# GNSS_OCXO.net
KiCad netlist of a schematic drawn in Altium Designer
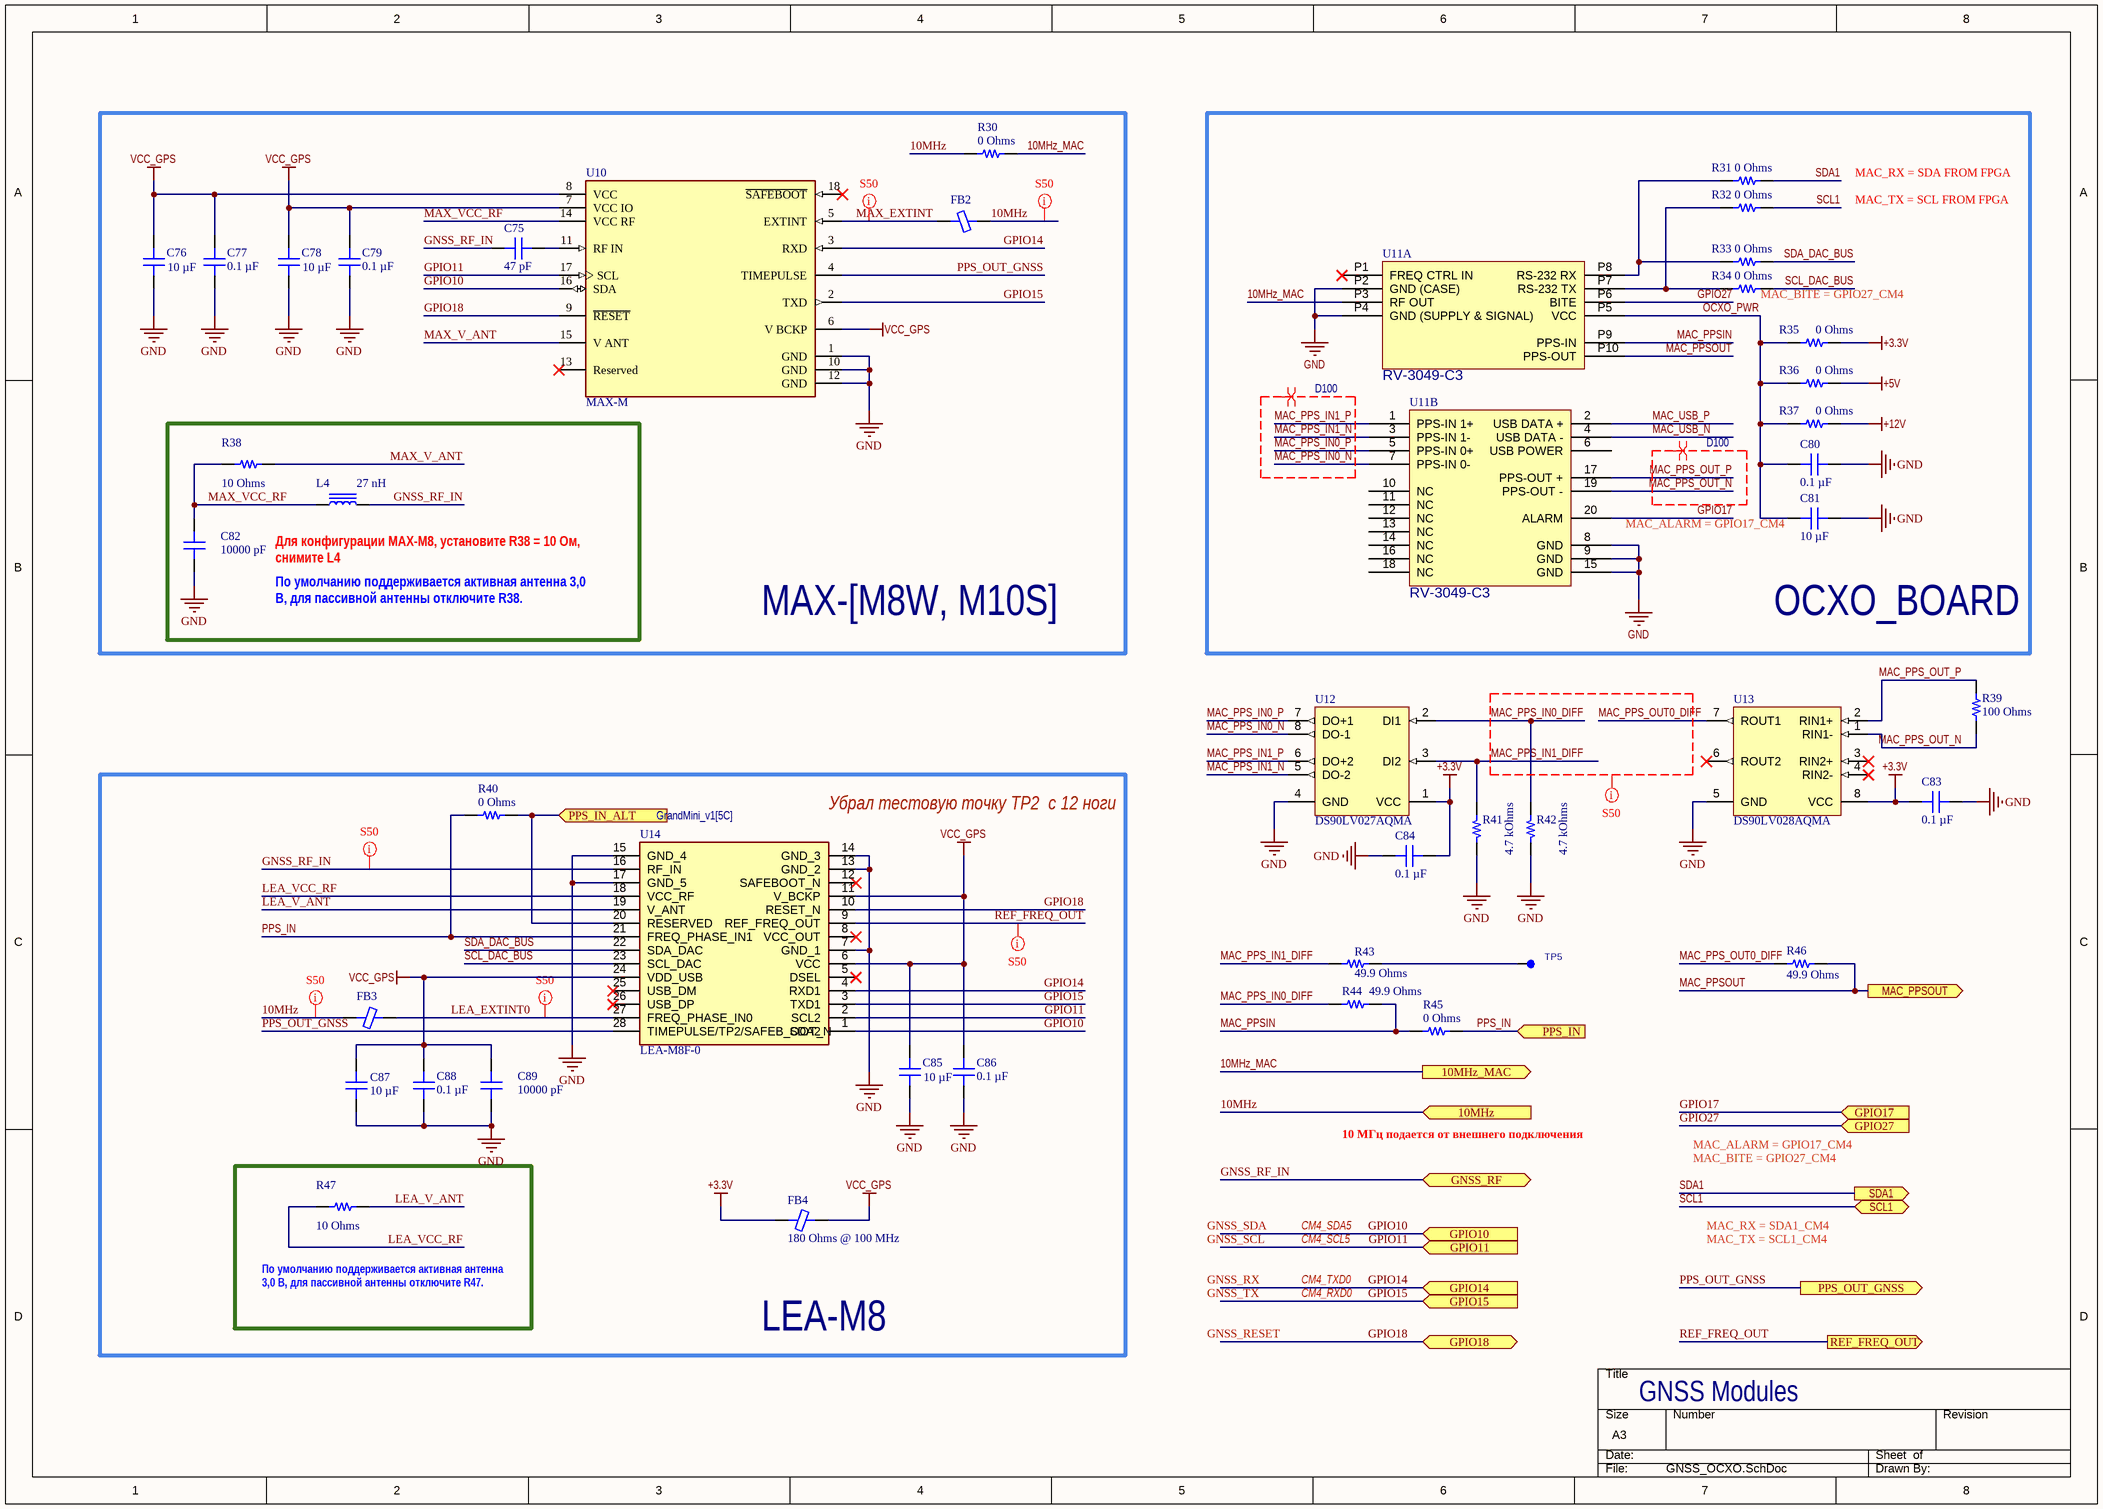
[diagram p0: GNSS_OCXO.SchDoc]

(export (version "E")
  (design (tool "Eeschema 10.0.6"))
  (components
    (comp (ref "C75")
      (value "47 pF")
      (footprint "CAP 0603_1608")
      (description "CAP CER 47PF 25V C0G/NPO 0603")
      (fields (field (name "MANUFACTURER") "Yageo") (field (name "TOLERANCE") "±5%"))
      (libsource (lib "Celestial Altium Library - altium_library") (part "Capacitor"))
    )
    (comp (ref "C76")
      (value "10 µF")
      (footprint "CAP 0805_2012")
      (description "CAP CER 10UF 25V X5R 0805")
      (fields
        (field (name "TOLERANCE") "±10%")
        (field (name "CAPACITANCE") "10 µF")
        (field (name "PART NUMBER") "CC0805KKX5R8BB106")
      )
      (libsource (lib "Celestial Altium Library - altium_library") (part "Capacitor"))
    )
    (comp (ref "C77")
      (value "0.1 µF")
      (footprint "CAP 0603_1608")
      (description "CAP CER 0.1UF 50V X7R 0603")
      (fields (field (name "MANUFACTURER") "Yageo") (field (name "TOLERANCE") "±10%"))
      (libsource (lib "Celestial Altium Library - altium_library") (part "Capacitor"))
    )
    (comp (ref "C78")
      (value "10 µF")
      (footprint "CAP 0805_2012")
      (description "CAP CER 10UF 25V X5R 0805")
      (fields
        (field (name "TOLERANCE") "±10%")
        (field (name "CAPACITANCE") "10 µF")
        (field (name "PART NUMBER") "CC0805KKX5R8BB106")
      )
      (libsource (lib "Celestial Altium Library - altium_library") (part "Capacitor"))
    )
    (comp (ref "C79")
      (value "0.1 µF")
      (footprint "CAP 0603_1608")
      (description "CAP CER 0.1UF 50V X7R 0603")
      (fields (field (name "MANUFACTURER") "Yageo") (field (name "TOLERANCE") "±10%"))
      (libsource (lib "Celestial Altium Library - altium_library") (part "Capacitor"))
    )
    (comp (ref "C80")
      (value "0.1 µF")
      (footprint "CAP 0603_1608")
      (description "CAP CER 0.1UF 50V X7R 0603")
      (fields (field (name "MANUFACTURER") "Yageo") (field (name "PART NUMBER") "CC0603KRX7R9BB104"))
      (libsource (lib "Celestial Altium Library - altium_library") (part "Capacitor"))
    )
    (comp (ref "C81")
      (value "10 µF")
      (footprint "CAP 0805_2012")
      (description "CAP CER 10UF 25V X5R 0805")
      (fields
        (field (name "TOLERANCE") "±10%")
        (field (name "CAPACITANCE") "10 µF")
        (field (name "PART NUMBER") "CC0805KKX5R8BB106")
      )
      (libsource (lib "Celestial Altium Library - altium_library") (part "Capacitor"))
    )
    (comp (ref "C82")
      (value "10000 pF")
      (footprint "CAP 0603_1608")
      (description "CAP CER 10000PF 50V X7R 0603")
      (fields (field (name "MANUFACTURER") "Yageo") (field (name "PART NUMBER") "CC0603KRX7R9BB103"))
      (libsource (lib "Celestial Altium Library - altium_library") (part "Capacitor"))
    )
    (comp (ref "C83")
      (value "0.1 µF")
      (footprint "CAP 0603_1608")
      (description "CAP CER 0.1UF 50V X7R 0603")
      (fields (field (name "MANUFACTURER") "Yageo") (field (name "PART NUMBER") "CC0603KRX7R9BB104"))
      (libsource (lib "Celestial Altium Library - altium_library") (part "Capacitor"))
    )
    (comp (ref "C84")
      (value "0.1 µF")
      (footprint "CAP 0603_1608")
      (description "CAP CER 0.1UF 50V X7R 0603")
      (fields (field (name "MANUFACTURER") "Yageo") (field (name "PART NUMBER") "CC0603KRX7R9BB104"))
      (libsource (lib "Celestial Altium Library - altium_library") (part "Capacitor"))
    )
    (comp (ref "C85")
      (value "10 µF")
      (footprint "CAP 0805_2012")
      (description "CAP CER 10UF 25V X5R 0805")
      (fields
        (field (name "TOLERANCE") "±10%")
        (field (name "CAPACITANCE") "10 µF")
        (field (name "PART NUMBER") "CC0805KKX5R8BB106")
      )
      (libsource (lib "Celestial Altium Library - altium_library") (part "Capacitor"))
    )
    (comp (ref "C86")
      (value "0.1 µF")
      (footprint "CAP 0603_1608")
      (description "CAP CER 0.1UF 50V X7R 0603")
      (fields (field (name "MANUFACTURER") "Yageo") (field (name "TOLERANCE") "±10%"))
      (libsource (lib "Celestial Altium Library - altium_library") (part "Capacitor"))
    )
    (comp (ref "C87")
      (value "10 µF")
      (footprint "CAP 0805_2012")
      (description "CAP CER 10UF 25V X5R 0805")
      (fields
        (field (name "TOLERANCE") "±10%")
        (field (name "CAPACITANCE") "10 µF")
        (field (name "PART NUMBER") "CC0805KKX5R8BB106")
      )
      (libsource (lib "Celestial Altium Library - altium_library") (part "Capacitor"))
    )
    (comp (ref "C88")
      (value "0.1 µF")
      (footprint "CAP 0603_1608")
      (description "CAP CER 0.1UF 50V X7R 0603")
      (fields (field (name "MANUFACTURER") "Yageo") (field (name "TOLERANCE") "±10%"))
      (libsource (lib "Celestial Altium Library - altium_library") (part "Capacitor"))
    )
    (comp (ref "C89")
      (value "10000 pF")
      (footprint "CAP 0603_1608")
      (description "CAP CER 10000PF 50V X7R 0603")
      (fields (field (name "MANUFACTURER") "Yageo") (field (name "PART NUMBER") "CC0603KRX7R9BB103"))
      (libsource (lib "Celestial Altium Library - altium_library") (part "Capacitor"))
    )
    (comp (ref "FB2")
      (value "1 kOhms @ 100 MHz")
      (footprint "FER 0603_1608")
      (description "FERRITE BEAD 1K OHM 0603 1LN")
      (fields
        (field (name "PART NUMBER") "BLM18HG102SH1D")
        (field (name "MANUFACTURER") "Murata Electronics")
      )
      (libsource (lib "Celestial Altium Library - altium_library") (part "Ferrite Chip"))
    )
    (comp (ref "FB3")
      (value "1 kOhms @ 100 MHz")
      (footprint "FER 0603_1608")
      (description "FERRITE BEAD 1K OHM 0603 1LN")
      (fields
        (field (name "PART NUMBER") "BLM18HG102SH1D")
        (field (name "MANUFACTURER") "Murata Electronics")
      )
      (libsource (lib "Celestial Altium Library - altium_library") (part "Ferrite Chip"))
    )
    (comp (ref "FB4")
      (value "180 Ohms @ 100 MHz")
      (footprint "FER 0603_1608")
      (description "FERRITE BEAD 180 OHM 0603 1LN")
      (fields
        (field (name "PART NUMBER") "BLM18PG181SN1D")
        (field (name "MANUFACTURER") "Murata Electronics")
      )
      (libsource (lib "Celestial Altium Library - altium_library") (part "Ferrite Chip"))
    )
    (comp (ref "L4")
      (value "27 nH")
      (footprint "Murata LQW18 0603")
      (description "FIXED IND 27NH 440MA 0.21OHM SMD")
      (fields (field (name "TOLERANCE") "±2%") (field (name "PART NUMBER") "LQW18AN27NG00D"))
      (libsource (lib "Celestial Altium Library - altium_library") (part "Inductor"))
    )
    (comp (ref "R30")
      (value "0 Ohms")
      (footprint "YAGEO RES 0603_1608")
      (description "RES 0 OHM JUMPER 1/10W 0603")
      (fields (field (name "TOLERANCE") "Jumper") (field (name "MANUFACTURER") "Yageo"))
      (libsource (lib "Celestial Altium Library - altium_library") (part "Resistor"))
    )
    (comp (ref "R31")
      (value "0 Ohms")
      (footprint "YAGEO RES 0603_1608")
      (description "RES 0 OHM JUMPER 1/10W 0603")
      (fields (field (name "PART NUMBER") "RC0603FR-070RL") (field (name "MANUFACTURER") "Yageo"))
      (libsource (lib "Celestial Altium Library - altium_library") (part "Resistor"))
    )
    (comp (ref "R32")
      (value "0 Ohms")
      (footprint "YAGEO RES 0603_1608")
      (description "RES 0 OHM JUMPER 1/10W 0603")
      (fields (field (name "PART NUMBER") "RC0603FR-070RL") (field (name "MANUFACTURER") "Yageo"))
      (libsource (lib "Celestial Altium Library - altium_library") (part "Resistor"))
    )
    (comp (ref "R33")
      (value "0 Ohms")
      (footprint "YAGEO RES 0603_1608")
      (description "RES 0 OHM JUMPER 1/10W 0603")
      (fields (field (name "PART NUMBER") "RC0603FR-070RL") (field (name "MANUFACTURER") "Yageo"))
      (libsource (lib "Celestial Altium Library - altium_library") (part "Resistor"))
    )
    (comp (ref "R34")
      (value "0 Ohms")
      (footprint "YAGEO RES 0603_1608")
      (description "RES 0 OHM JUMPER 1/10W 0603")
      (fields (field (name "PART NUMBER") "RC0603FR-070RL") (field (name "MANUFACTURER") "Yageo"))
      (libsource (lib "Celestial Altium Library - altium_library") (part "Resistor"))
    )
    (comp (ref "R35")
      (value "0 Ohms")
      (footprint "YAGEO RES 0603_1608")
      (description "RES 0 OHM JUMPER 1/10W 0603")
      (fields (field (name "PART NUMBER") "RC0603FR-070RL") (field (name "MANUFACTURER") "Yageo"))
      (libsource (lib "Celestial Altium Library - altium_library") (part "Resistor"))
    )
    (comp (ref "R36")
      (value "0 Ohms")
      (footprint "YAGEO RES 0603_1608")
      (description "RES 0 OHM JUMPER 1/10W 0603")
      (fields (field (name "PART NUMBER") "RC0603FR-070RL") (field (name "MANUFACTURER") "Yageo"))
      (libsource (lib "Celestial Altium Library - altium_library") (part "Resistor"))
    )
    (comp (ref "R37")
      (value "0 Ohms")
      (footprint "YAGEO RES 0603_1608")
      (description "RES 0 OHM JUMPER 1/10W 0603")
      (fields (field (name "PART NUMBER") "RC0603FR-070RL") (field (name "MANUFACTURER") "Yageo"))
      (libsource (lib "Celestial Altium Library - altium_library") (part "Resistor"))
    )
    (comp (ref "R38")
      (value "10 Ohms")
      (footprint "YAGEO RES 0603_1608")
      (description "RES 10 OHM 1% 1/10W 0603")
      (fields (field (name "MANUFACTURER") "Yageo") (field (name "TOLERANCE") "±1%"))
      (libsource (lib "Celestial Altium Library - altium_library") (part "Resistor"))
    )
    (comp (ref "R39")
      (value "100 Ohms")
      (footprint "YAGEO RES 0603_1608")
      (description "RES 100 OHM 1% 1/10W 0603")
      (fields (field (name "PART NUMBER") "RC0603FR-07100RL") (field (name "MANUFACTURER") "Yageo"))
      (libsource (lib "Celestial Altium Library - altium_library") (part "Resistor"))
    )
    (comp (ref "R40")
      (value "0 Ohms")
      (footprint "YAGEO RES 0603_1608")
      (description "RES 0 OHM JUMPER 1/10W 0603")
      (fields (field (name "TOLERANCE") "Jumper") (field (name "MANUFACTURER") "Yageo"))
      (libsource (lib "Celestial Altium Library - altium_library") (part "Resistor"))
    )
    (comp (ref "R41")
      (value "4.7 kOhms")
      (footprint "YAGEO RES 0402_1005")
      (description "RES 4.7K OHM 1% 1/16W 0402")
      (fields (field (name "MANUFACTURER") "Yageo") (field (name "TOLERANCE") "±1%"))
      (libsource (lib "Celestial Altium Library - altium_library") (part "Resistor"))
    )
    (comp (ref "R42")
      (value "4.7 kOhms")
      (footprint "YAGEO RES 0402_1005")
      (description "RES 4.7K OHM 1% 1/16W 0402")
      (fields (field (name "MANUFACTURER") "Yageo") (field (name "TOLERANCE") "±1%"))
      (libsource (lib "Celestial Altium Library - altium_library") (part "Resistor"))
    )
    (comp (ref "R43")
      (value "49.9 Ohms")
      (footprint "YAGEO RES 0603_1608")
      (description "RES 49.9 OHM 1% 1/10W 0603")
      (fields (field (name "PART NUMBER") "RC0603FR-0749R9L") (field (name "MANUFACTURER") "Yageo"))
      (libsource (lib "Celestial Altium Library - altium_library") (part "Resistor"))
    )
    (comp (ref "R44")
      (value "49.9 Ohms")
      (footprint "YAGEO RES 0603_1608")
      (description "RES 49.9 OHM 1% 1/10W 0603")
      (fields (field (name "PART NUMBER") "RC0603FR-0749R9L") (field (name "MANUFACTURER") "Yageo"))
      (libsource (lib "Celestial Altium Library - altium_library") (part "Resistor"))
    )
    (comp (ref "R45")
      (value "0 Ohms")
      (footprint "YAGEO RES 0603_1608")
      (description "RES 0 OHM JUMPER 1/10W 0603")
      (fields (field (name "TOLERANCE") "Jumper") (field (name "MANUFACTURER") "Yageo"))
      (libsource (lib "Celestial Altium Library - altium_library") (part "Resistor"))
    )
    (comp (ref "R46")
      (value "49.9 Ohms")
      (footprint "YAGEO RES 0603_1608")
      (description "RES 49.9 OHM 1% 1/10W 0603")
      (fields (field (name "PART NUMBER") "RC0603FR-0749R9L") (field (name "MANUFACTURER") "Yageo"))
      (libsource (lib "Celestial Altium Library - altium_library") (part "Resistor"))
    )
    (comp (ref "R47")
      (value "10 Ohms")
      (footprint "YAGEO RES 0603_1608")
      (description "RES 10 OHM 1% 1/10W 0603")
      (fields (field (name "MANUFACTURER") "Yageo") (field (name "TOLERANCE") "±1%"))
      (libsource (lib "Celestial Altium Library - altium_library") (part "Resistor"))
    )
    (comp (ref "TP5")
      (value "PAD_TEST")
      (footprint "Samacsys:PAD_TEST")
      (description "Test Point")
      (fields (field (name "TOLERANCE") "{Tolerance}") (field (name "MANUFACTURER") "{Manufacturer}"))
      (libsource (lib "SamacSys") (part "PAD_TEST"))
    )
    (comp (ref "U10")
      (value "MAX-M")
      (footprint "FP-MAX-M8W-0-MFG")
      (description "RF RCVR GNSS/GPS 1.575GHZ 18LCC")
      (libsource (lib "Altium Content Vault") (part "36e94f557bbf38d877319147cff7e99"))
    )
    (comp (ref "U11")
      (value "RV-3049-C3")
      (footprint "OCXO_CARD")
      (description "MOD, MAC, MAC-SA5X, ATOMIC CLOCK")
      (fields (field (name "MFG PART NUM") "MAC-SA5X") (field (name "VELENTIUM PART NUM") "<V PART NUM>"))
      (libsource (lib "SHIWA_lib") (part "MAC-SA5X"))
    )
    (comp (ref "U12")
      (value "DS90LV027AQMA")
      (footprint "M08A_N")
      (description "Automotive LVDS Dual Differential Driver, 8-pin Narrow SOIC")
      (fields (field (name "MANUFACTURER") "National Semiconductor"))
      (libsource (lib "Altium Content Vault") (part "IN-LNDRV-DS90LV027AHM"))
    )
    (comp (ref "U13")
      (value "DS90LV028AQMA")
      (footprint "M08A_L")
      (description "Automotive LVDS Dual Differential Line Receiver, 8-pin Narrow SOIC")
      (fields (field (name "MANUFACTURER") "National Semiconductor"))
      (libsource (lib "Altium Content Vault") (part "IN-LNRX-DS90LV028AHM"))
    )
    (comp (ref "U14")
      (value "LEA-M8F-0")
      (footprint "SamacSys:LEAM8F0")
      (description "Integrated Circuit")
      (fields (field (name "MOUSER PART NUMBER") "377-LEA-M8F-0"))
      (libsource (lib "SamacSys") (part "LEA-M8F-0"))
    )
  )
  (nets
    (net (code "1") (name "+3.3V") (class "Default")
      (node (ref "C83") (pin "1") (pinfunction "1_1") (pintype "passive"))
      (node (ref "C84") (pin "2") (pinfunction "2_2") (pintype "passive"))
      (node (ref "FB4") (pin "1") (pinfunction "1_1") (pintype "passive"))
      (node (ref "R35") (pin "1") (pinfunction "1_1") (pintype "passive"))
      (node (ref "U12") (pin "1") (pinfunction "VCC_1") (pintype "power_in"))
      (node (ref "U13") (pin "8") (pinfunction "VCC_8") (pintype "power_in"))
    )
    (net (code "2") (name "+5V") (class "Default")
      (node (ref "R36") (pin "1") (pinfunction "1_1") (pintype "passive"))
    )
    (net (code "3") (name "+12V") (class "Default")
      (node (ref "R37") (pin "1") (pinfunction "1_1") (pintype "passive"))
    )
    (net (code "4") (name "/10MHz") (class "Default")
      (node (ref "FB2") (pin "1") (pinfunction "1_1") (pintype "passive"))
      (node (ref "FB3") (pin "1") (pinfunction "1_1") (pintype "passive"))
      (node (ref "R30") (pin "1") (pinfunction "1_1") (pintype "passive"))
    )
    (net (code "5") (name "/10MHz_MAC") (class "Default")
      (node (ref "R30") (pin "2") (pinfunction "2_2") (pintype "passive"))
      (node (ref "U11") (pin "P3") (pinfunction "RF_OUT_P3") (pintype "passive"))
    )
    (net (code "6") (name "/GNSS_RF_IN") (class "Default")
      (node (ref "C75") (pin "1") (pinfunction "1_1") (pintype "passive"))
      (node (ref "L4") (pin "2") (pinfunction "2_2") (pintype "passive"))
      (node (ref "U14") (pin "16") (pinfunction "RF_IN_16") (pintype "passive"))
    )
    (net (code "7") (name "/GPIO10") (class "Default")
      (node (ref "U10") (pin "16") (pinfunction "SDA_16") (pintype "bidirectional"))
      (node (ref "U14") (pin "1") (pinfunction "SDA2_1") (pintype "passive"))
    )
    (net (code "8") (name "/GPIO11") (class "Default")
      (node (ref "U10") (pin "17") (pinfunction "SCL_17") (pintype "input"))
      (node (ref "U14") (pin "2") (pinfunction "SCL2_2") (pintype "passive"))
    )
    (net (code "9") (name "/GPIO14") (class "Default")
      (node (ref "U10") (pin "3") (pinfunction "RXD_3") (pintype "input"))
      (node (ref "U14") (pin "4") (pinfunction "RXD1_4") (pintype "passive"))
    )
    (net (code "10") (name "/GPIO15") (class "Default")
      (node (ref "U10") (pin "2") (pinfunction "TXD_2") (pintype "output"))
      (node (ref "U14") (pin "3") (pinfunction "TXD1_3") (pintype "passive"))
    )
    (net (code "11") (name "/GPIO17") (class "Default")
      (node (ref "U11") (pin "20") (pinfunction "ALARM_20") (pintype "passive"))
    )
    (net (code "12") (name "/GPIO18") (class "Default")
      (node (ref "U10") (pin "9") (pinfunction "~{RESET}_9") (pintype "passive"))
      (node (ref "U14") (pin "10") (pinfunction "RESET_N_10") (pintype "passive"))
    )
    (net (code "13") (name "/GPIO27") (class "Default")
      (node (ref "U11") (pin "P6") (pinfunction "BITE_P6") (pintype "passive"))
    )
    (net (code "14") (name "/LEA_EXTINT0") (class "Default")
      (node (ref "FB3") (pin "2") (pinfunction "2_2") (pintype "passive"))
      (node (ref "U14") (pin "27") (pinfunction "FREQ_PHASE_IN0_27") (pintype "passive"))
    )
    (net (code "15") (name "/LEA_VCC_RF") (class "Default")
      (node (ref "R47") (pin "1") (pinfunction "1_1") (pintype "passive"))
      (node (ref "U14") (pin "18") (pinfunction "VCC_RF_18") (pintype "passive"))
    )
    (net (code "16") (name "/LEA_V_ANT") (class "Default")
      (node (ref "R47") (pin "2") (pinfunction "2_2") (pintype "passive"))
      (node (ref "U14") (pin "19") (pinfunction "V_ANT_19") (pintype "passive"))
    )
    (net (code "17") (name "/MAC_PPSIN") (class "Default")
      (node (ref "R44") (pin "2") (pinfunction "2_2") (pintype "passive"))
      (node (ref "R45") (pin "1") (pinfunction "1_1") (pintype "passive"))
      (node (ref "U11") (pin "P9") (pinfunction "PPS-IN_P9") (pintype "passive"))
    )
    (net (code "18") (name "/MAC_PPSOUT") (class "Default")
      (node (ref "R46") (pin "2") (pinfunction "2_2") (pintype "passive"))
      (node (ref "U11") (pin "P10") (pinfunction "PPS-OUT_P10") (pintype "passive"))
    )
    (net (code "19") (name "/MAC_PPS_IN0_DIFF") (class "Default")
      (node (ref "R42") (pin "2") (pinfunction "2_2") (pintype "passive"))
      (node (ref "R44") (pin "1") (pinfunction "1_1") (pintype "passive"))
      (node (ref "U12") (pin "2") (pinfunction "DI1_2") (pintype "input"))
    )
    (net (code "20") (name "/MAC_PPS_IN0_N") (class "Default")
      (node (ref "U11") (pin "7") (pinfunction "PPS-IN_0-_7") (pintype "passive"))
      (node (ref "U12") (pin "8") (pinfunction "DO-1_8") (pintype "output"))
    )
    (net (code "21") (name "/MAC_PPS_IN0_P") (class "Default")
      (node (ref "U11") (pin "5") (pinfunction "PPS-IN_0+_5") (pintype "passive"))
      (node (ref "U12") (pin "7") (pinfunction "DO+1_7") (pintype "output"))
    )
    (net (code "22") (name "/MAC_PPS_IN1_DIFF") (class "Default")
      (node (ref "R41") (pin "2") (pinfunction "2_2") (pintype "passive"))
      (node (ref "R43") (pin "1") (pinfunction "1_1") (pintype "passive"))
      (node (ref "U12") (pin "3") (pinfunction "DI2_3") (pintype "input"))
    )
    (net (code "23") (name "/MAC_PPS_IN1_N") (class "Default")
      (node (ref "U11") (pin "3") (pinfunction "PPS-IN_1-_3") (pintype "passive"))
      (node (ref "U12") (pin "5") (pinfunction "DO-2_5") (pintype "output"))
    )
    (net (code "24") (name "/MAC_PPS_IN1_P") (class "Default")
      (node (ref "U11") (pin "1") (pinfunction "PPS-IN_1+_1") (pintype "passive"))
      (node (ref "U12") (pin "6") (pinfunction "DO+2_6") (pintype "output"))
    )
    (net (code "25") (name "/MAC_PPS_OUT0_DIFF") (class "Default")
      (node (ref "R46") (pin "1") (pinfunction "1_1") (pintype "passive"))
      (node (ref "U13") (pin "7") (pinfunction "ROUT1_7") (pintype "output"))
    )
    (net (code "26") (name "/MAC_PPS_OUT_N") (class "Default")
      (node (ref "R39") (pin "1") (pinfunction "1_1") (pintype "passive"))
      (node (ref "U11") (pin "19") (pinfunction "PPS-OUT_-_19") (pintype "passive"))
      (node (ref "U13") (pin "1") (pinfunction "RIN1-_1") (pintype "input"))
    )
    (net (code "27") (name "/MAC_PPS_OUT_P") (class "Default")
      (node (ref "R39") (pin "2") (pinfunction "2_2") (pintype "passive"))
      (node (ref "U11") (pin "17") (pinfunction "PPS-OUT_+_17") (pintype "passive"))
      (node (ref "U13") (pin "2") (pinfunction "RIN1+_2") (pintype "input"))
    )
    (net (code "28") (name "/MAC_USB_N") (class "Default")
      (node (ref "U11") (pin "4") (pinfunction "USB_DATA_-_4") (pintype "passive"))
    )
    (net (code "29") (name "/MAC_USB_P") (class "Default")
      (node (ref "U11") (pin "2") (pinfunction "USB_DATA_+_2") (pintype "passive"))
    )
    (net (code "30") (name "/MAX_EXTINT") (class "Default")
      (node (ref "FB2") (pin "2") (pinfunction "2_2") (pintype "passive"))
      (node (ref "U10") (pin "5") (pinfunction "EXTINT_5") (pintype "input"))
    )
    (net (code "31") (name "/MAX_VCC_RF") (class "Default")
      (node (ref "C82") (pin "2") (pinfunction "2_2") (pintype "passive"))
      (node (ref "L4") (pin "1") (pinfunction "1_1") (pintype "passive"))
      (node (ref "R38") (pin "1") (pinfunction "1_1") (pintype "passive"))
      (node (ref "U10") (pin "14") (pinfunction "VCC_RF_14") (pintype "power_in"))
    )
    (net (code "32") (name "/MAX_V_ANT") (class "Default")
      (node (ref "R38") (pin "2") (pinfunction "2_2") (pintype "passive"))
      (node (ref "U10") (pin "15") (pinfunction "V_ANT_15") (pintype "power_in"))
    )
    (net (code "33") (name "/OCXO_PWR") (class "Default")
      (node (ref "C80") (pin "1") (pinfunction "1_1") (pintype "passive"))
      (node (ref "C81") (pin "2") (pinfunction "2_2") (pintype "passive"))
      (node (ref "R35") (pin "2") (pinfunction "2_2") (pintype "passive"))
      (node (ref "R36") (pin "2") (pinfunction "2_2") (pintype "passive"))
      (node (ref "R37") (pin "2") (pinfunction "2_2") (pintype "passive"))
      (node (ref "U11") (pin "P5") (pinfunction "VCC_P5") (pintype "passive"))
    )
    (net (code "34") (name "/PPS_IN") (class "Default")
      (node (ref "R40") (pin "1") (pinfunction "1_1") (pintype "passive"))
      (node (ref "R45") (pin "2") (pinfunction "2_2") (pintype "passive"))
      (node (ref "U14") (pin "21") (pinfunction "FREQ_PHASE_IN1_21") (pintype "passive"))
    )
    (net (code "35") (name "/PPS_IN_ALT") (class "Default")
      (node (ref "R40") (pin "2") (pinfunction "2_2") (pintype "passive"))
      (node (ref "U14") (pin "20") (pinfunction "RESERVED_20") (pintype "passive"))
    )
    (net (code "36") (name "/PPS_OUT_GNSS") (class "Default")
      (node (ref "U10") (pin "4") (pinfunction "TIMEPULSE_4") (pintype "passive"))
      (node (ref "U14") (pin "28") (pinfunction "TIMEPULSE/TP2/SAFEB_OOT_N_28") (pintype "passive"))
    )
    (net (code "37") (name "/REF_FREQ_OUT") (class "Default")
      (node (ref "U14") (pin "9") (pinfunction "REF_FREQ_OUT_9") (pintype "passive"))
    )
    (net (code "38") (name "/SCL1") (class "Default")
      (node (ref "R32") (pin "1") (pinfunction "1_1") (pintype "passive"))
    )
    (net (code "39") (name "/SCL_DAC_BUS") (class "Default")
      (node (ref "R34") (pin "1") (pinfunction "1_1") (pintype "passive"))
      (node (ref "U14") (pin "23") (pinfunction "SCL_DAC_23") (pintype "passive"))
    )
    (net (code "40") (name "/SDA1") (class "Default")
      (node (ref "R31") (pin "1") (pinfunction "1_1") (pintype "passive"))
    )
    (net (code "41") (name "/SDA_DAC_BUS") (class "Default")
      (node (ref "R33") (pin "1") (pinfunction "1_1") (pintype "passive"))
      (node (ref "U14") (pin "22") (pinfunction "SDA_DAC_22") (pintype "passive"))
    )
    (net (code "42") (name "GND") (class "Default")
      (node (ref "C76") (pin "1") (pinfunction "1_1") (pintype "passive"))
      (node (ref "C77") (pin "1") (pinfunction "1_1") (pintype "passive"))
      (node (ref "C78") (pin "1") (pinfunction "1_1") (pintype "passive"))
      (node (ref "C79") (pin "1") (pinfunction "1_1") (pintype "passive"))
      (node (ref "C80") (pin "2") (pinfunction "2_2") (pintype "passive"))
      (node (ref "C81") (pin "1") (pinfunction "1_1") (pintype "passive"))
      (node (ref "C82") (pin "1") (pinfunction "1_1") (pintype "passive"))
      (node (ref "C83") (pin "2") (pinfunction "2_2") (pintype "passive"))
      (node (ref "C84") (pin "1") (pinfunction "1_1") (pintype "passive"))
      (node (ref "C85") (pin "1") (pinfunction "1_1") (pintype "passive"))
      (node (ref "C86") (pin "1") (pinfunction "1_1") (pintype "passive"))
      (node (ref "C87") (pin "1") (pinfunction "1_1") (pintype "passive"))
      (node (ref "C88") (pin "1") (pinfunction "1_1") (pintype "passive"))
      (node (ref "C89") (pin "1") (pinfunction "1_1") (pintype "passive"))
      (node (ref "R41") (pin "1") (pinfunction "1_1") (pintype "passive"))
      (node (ref "R42") (pin "1") (pinfunction "1_1") (pintype "passive"))
      (node (ref "U10") (pin "1") (pinfunction "GND_1") (pintype "power_in"))
      (node (ref "U10") (pin "10") (pinfunction "GND_10") (pintype "power_in"))
      (node (ref "U10") (pin "12") (pinfunction "GND_12") (pintype "power_in"))
      (node (ref "U11") (pin "15") (pinfunction "GND_15") (pintype "passive"))
      (node (ref "U11") (pin "8") (pinfunction "GND_8") (pintype "passive"))
      (node (ref "U11") (pin "9") (pinfunction "GND_9") (pintype "passive"))
      (node (ref "U11") (pin "P2") (pinfunction "GND_(CASE)_P2") (pintype "passive"))
      (node (ref "U11") (pin "P4") (pinfunction "GND_(SUPPLY_&_SIGNAL)_P4") (pintype "passive"))
      (node (ref "U12") (pin "4") (pinfunction "GND_4") (pintype "power_in"))
      (node (ref "U13") (pin "5") (pinfunction "GND_5") (pintype "power_in"))
      (node (ref "U14") (pin "13") (pinfunction "GND_2_13") (pintype "passive"))
      (node (ref "U14") (pin "14") (pinfunction "GND_3_14") (pintype "passive"))
      (node (ref "U14") (pin "15") (pinfunction "GND_4_15") (pintype "passive"))
      (node (ref "U14") (pin "17") (pinfunction "GND_5_17") (pintype "passive"))
      (node (ref "U14") (pin "7") (pinfunction "GND_1_7") (pintype "passive"))
    )
    (net (code "43") (name "Net-(R43-Pad2)") (class "Default")
      (node (ref "R43") (pin "2") (pinfunction "2_2") (pintype "passive"))
      (node (ref "TP5") (pin "1") (pinfunction "1_1") (pintype "passive"))
    )
    (net (code "44") (name "Net-(U10-RF_IN)") (class "Default")
      (node (ref "C75") (pin "2") (pinfunction "2_2") (pintype "passive"))
      (node (ref "U10") (pin "11") (pinfunction "RF_IN_11") (pintype "input"))
    )
    (net (code "45") (name "Net-(U11A-RS-232_RX)") (class "Default")
      (node (ref "R31") (pin "2") (pinfunction "2_2") (pintype "passive"))
      (node (ref "R33") (pin "2") (pinfunction "2_2") (pintype "passive"))
      (node (ref "U11") (pin "P8") (pinfunction "RS-232_RX_P8") (pintype "passive"))
    )
    (net (code "46") (name "Net-(U11A-RS-232_TX)") (class "Default")
      (node (ref "R32") (pin "2") (pinfunction "2_2") (pintype "passive"))
      (node (ref "R34") (pin "2") (pinfunction "2_2") (pintype "passive"))
      (node (ref "U11") (pin "P7") (pinfunction "RS-232_TX_P7") (pintype "passive"))
    )
    (net (code "47") (name "VCC_GPS") (class "Default")
      (node (ref "C76") (pin "2") (pinfunction "2_2") (pintype "passive"))
      (node (ref "C77") (pin "2") (pinfunction "2_2") (pintype "passive"))
      (node (ref "C78") (pin "2") (pinfunction "2_2") (pintype "passive"))
      (node (ref "C79") (pin "2") (pinfunction "2_2") (pintype "passive"))
      (node (ref "C85") (pin "2") (pinfunction "2_2") (pintype "passive"))
      (node (ref "C86") (pin "2") (pinfunction "2_2") (pintype "passive"))
      (node (ref "C87") (pin "2") (pinfunction "2_2") (pintype "passive"))
      (node (ref "C88") (pin "2") (pinfunction "2_2") (pintype "passive"))
      (node (ref "C89") (pin "2") (pinfunction "2_2") (pintype "passive"))
      (node (ref "FB4") (pin "2") (pinfunction "2_2") (pintype "passive"))
      (node (ref "U10") (pin "6") (pinfunction "V_BCKP_6") (pintype "power_in"))
      (node (ref "U10") (pin "7") (pinfunction "VCC_IO_7") (pintype "power_in"))
      (node (ref "U10") (pin "8") (pinfunction "VCC_8") (pintype "power_in"))
      (node (ref "U14") (pin "11") (pinfunction "V_BCKP_11") (pintype "passive"))
      (node (ref "U14") (pin "24") (pinfunction "VDD_USB_24") (pintype "passive"))
      (node (ref "U14") (pin "6") (pinfunction "VCC_6") (pintype "passive"))
    )
    (net (code "48") (name "unconnected-(U10-Reserved-Pad13)") (class "Default")
      (node (ref "U10") (pin "13") (pinfunction "Reserved_13") (pintype "passive+no_connect"))
    )
    (net (code "49") (name "unconnected-(U10-~{SAFEBOOT}-Pad18)") (class "Default")
      (node (ref "U10") (pin "18") (pinfunction "~{SAFEBOOT}_18") (pintype "input+no_connect"))
    )
    (net (code "50") (name "unconnected-(U11A-FREQ_CTRL_IN-PadP1)") (class "Default")
      (node (ref "U11") (pin "P1") (pinfunction "FREQ_CTRL_IN_P1") (pintype "passive+no_connect"))
    )
    (net (code "51") (name "unconnected-(U11B-NC-Pad10)") (class "Default")
      (node (ref "U11") (pin "10") (pinfunction "NC_10") (pintype "passive"))
    )
    (net (code "52") (name "unconnected-(U11B-NC-Pad11)") (class "Default")
      (node (ref "U11") (pin "11") (pinfunction "NC_11") (pintype "passive"))
    )
    (net (code "53") (name "unconnected-(U11B-NC-Pad12)") (class "Default")
      (node (ref "U11") (pin "12") (pinfunction "NC_12") (pintype "passive"))
    )
    (net (code "54") (name "unconnected-(U11B-NC-Pad13)") (class "Default")
      (node (ref "U11") (pin "13") (pinfunction "NC_13") (pintype "passive"))
    )
    (net (code "55") (name "unconnected-(U11B-NC-Pad14)") (class "Default")
      (node (ref "U11") (pin "14") (pinfunction "NC_14") (pintype "passive"))
    )
    (net (code "56") (name "unconnected-(U11B-NC-Pad16)") (class "Default")
      (node (ref "U11") (pin "16") (pinfunction "NC_16") (pintype "passive"))
    )
    (net (code "57") (name "unconnected-(U11B-NC-Pad18)") (class "Default")
      (node (ref "U11") (pin "18") (pinfunction "NC_18") (pintype "passive"))
    )
    (net (code "58") (name "unconnected-(U11B-USB_POWER-Pad6)") (class "Default")
      (node (ref "U11") (pin "6") (pinfunction "USB_POWER_6") (pintype "passive"))
    )
    (net (code "59") (name "unconnected-(U13-RIN2+-Pad3)") (class "Default")
      (node (ref "U13") (pin "3") (pinfunction "RIN2+_3") (pintype "input+no_connect"))
    )
    (net (code "60") (name "unconnected-(U13-RIN2--Pad4)") (class "Default")
      (node (ref "U13") (pin "4") (pinfunction "RIN2-_4") (pintype "input+no_connect"))
    )
    (net (code "61") (name "unconnected-(U13-ROUT2-Pad6)") (class "Default")
      (node (ref "U13") (pin "6") (pinfunction "ROUT2_6") (pintype "output+no_connect"))
    )
    (net (code "62") (name "unconnected-(U14-DSEL-Pad5)") (class "Default")
      (node (ref "U14") (pin "5") (pinfunction "DSEL_5") (pintype "passive+no_connect"))
    )
    (net (code "63") (name "unconnected-(U14-SAFEBOOT_N-Pad12)") (class "Default")
      (node (ref "U14") (pin "12") (pinfunction "SAFEBOOT_N_12") (pintype "passive+no_connect"))
    )
    (net (code "64") (name "unconnected-(U14-USB_DM-Pad25)") (class "Default")
      (node (ref "U14") (pin "25") (pinfunction "USB_DM_25") (pintype "passive+no_connect"))
    )
    (net (code "65") (name "unconnected-(U14-USB_DP-Pad26)") (class "Default")
      (node (ref "U14") (pin "26") (pinfunction "USB_DP_26") (pintype "passive+no_connect"))
    )
    (net (code "66") (name "unconnected-(U14-VCC_OUT-Pad8)") (class "Default")
      (node (ref "U14") (pin "8") (pinfunction "VCC_OUT_8") (pintype "passive+no_connect"))
    )
  )
)
